# preamp.net
KiCad netlist of a schematic drawn in Altium Designer
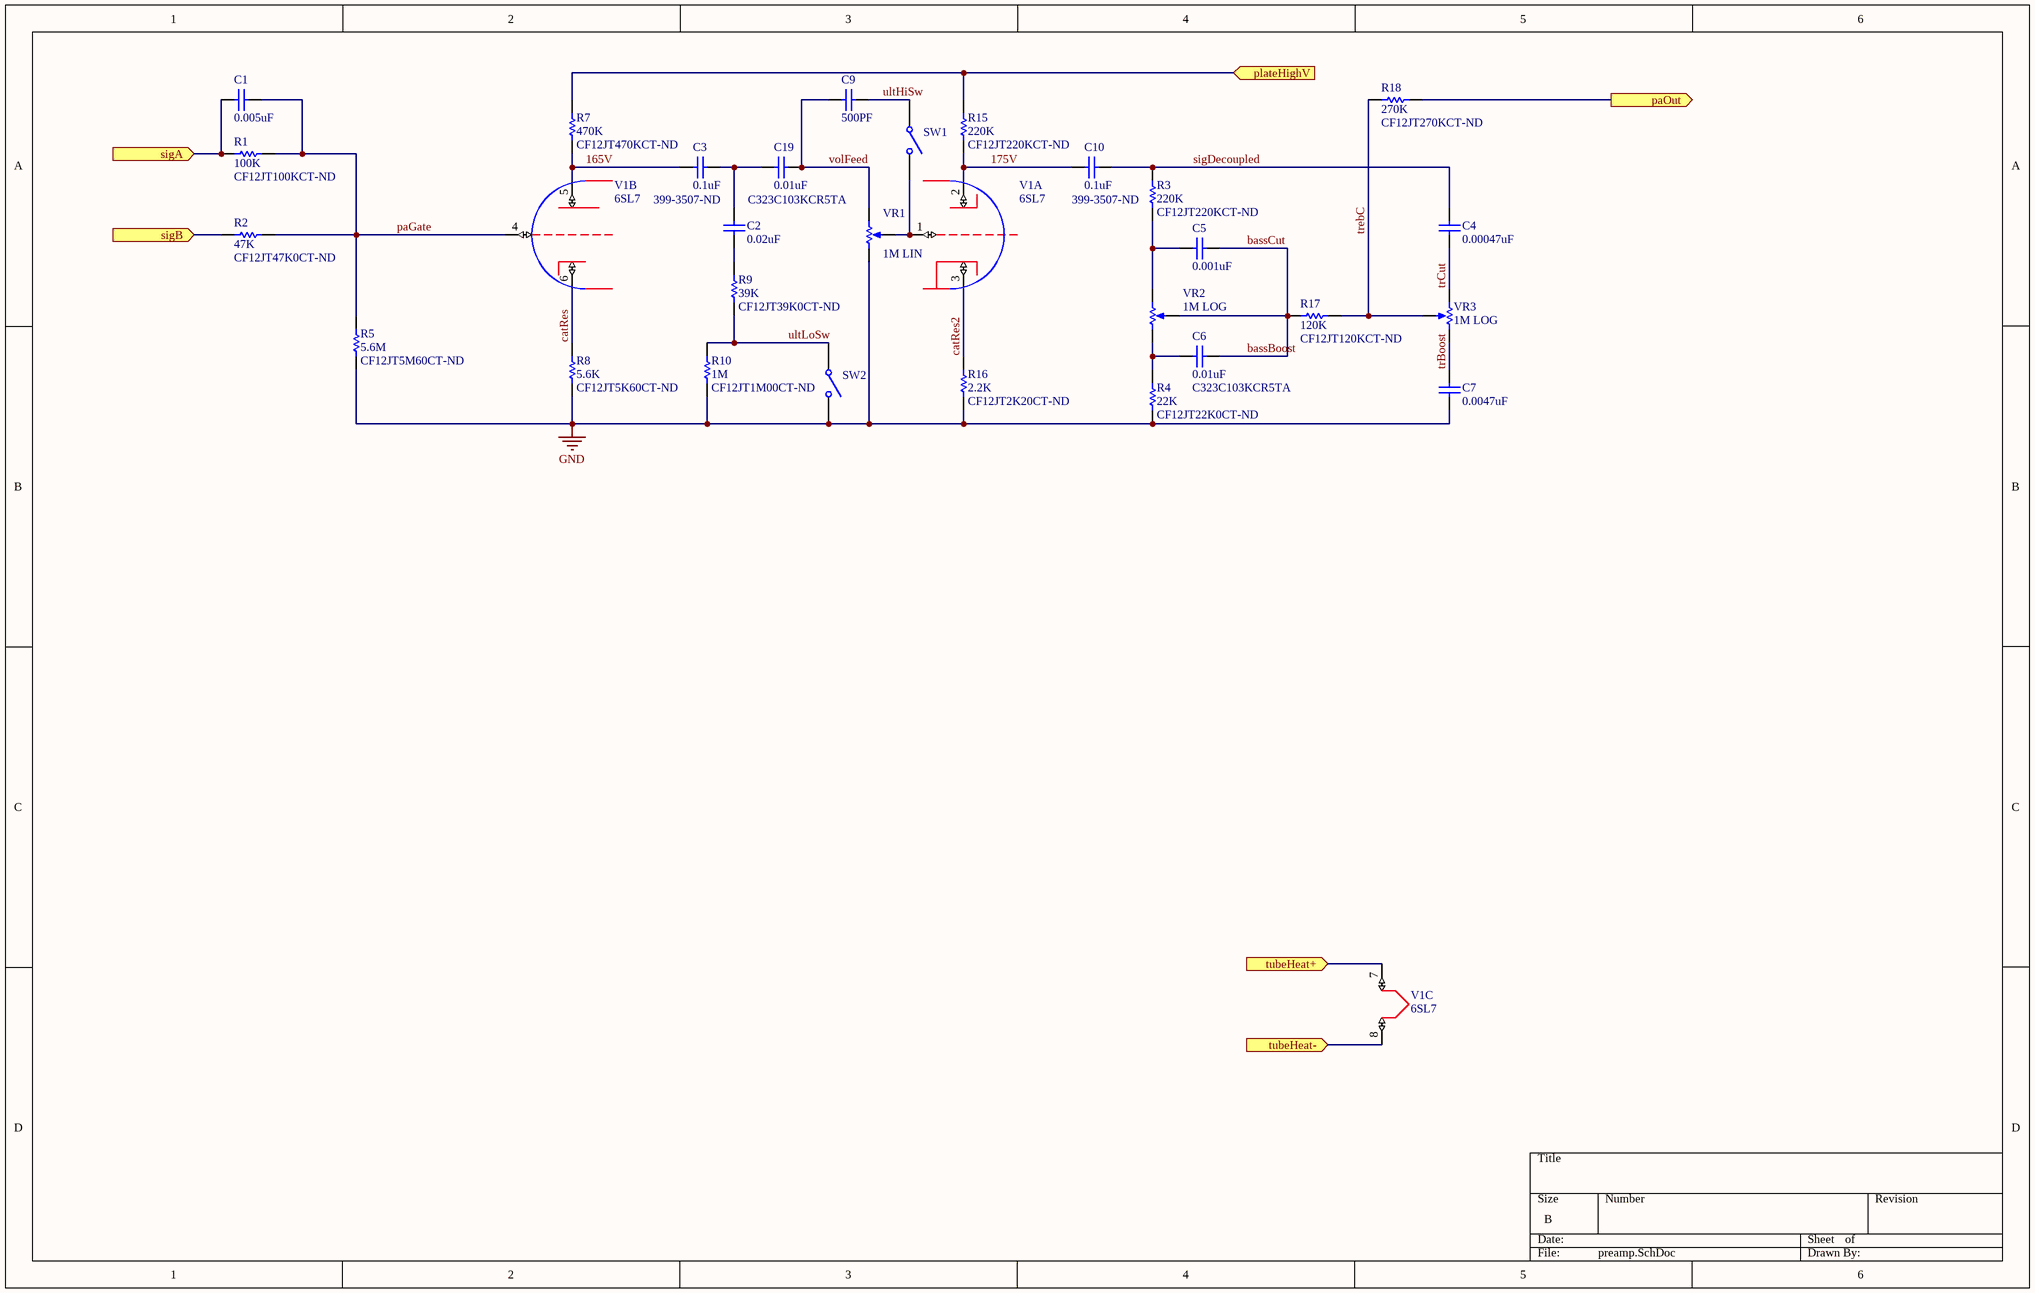
[diagram p0: preamp.SchDoc]

(export (version "E")
  (design (tool "Eeschema 10.0.6"))
  (components
    (comp (ref "C1")
      (value "0.005uF")
      (footprint "RAD-0.3")
      (description "Capacitor")
      (fields (field (name "Comment") "Cap") (field (name "PUBLISHER") "Altium Limited"))
      (libsource (lib "Miscellaneous Devices") (part "Cap"))
    )
    (comp (ref "C2")
      (value "0.02uF")
      (footprint "RAD-0.3")
      (description "Capacitor")
      (fields (field (name "Comment") "Cap") (field (name "PUBLISHER") "Altium Limited"))
      (libsource (lib "Miscellaneous Devices") (part "Cap"))
    )
    (comp (ref "C3")
      (value "0.1uF")
      (footprint "RAD-0.3")
      (description "Capacitor")
      (fields
        (field (name "SUPPLIER PART NUMBER 1") "399-3507-ND")
        (field (name "Comment") "Cap")
        (field (name "PUBLISHER") "Altium Limited")
      )
      (libsource (lib "Miscellaneous Devices") (part "Cap"))
    )
    (comp (ref "C4")
      (value "0.00047uF")
      (footprint "RAD-0.3")
      (description "Capacitor")
      (fields (field (name "Comment") "Cap") (field (name "PUBLISHER") "Altium Limited"))
      (libsource (lib "Miscellaneous Devices") (part "Cap"))
    )
    (comp (ref "C5")
      (value "0.001uF")
      (footprint "RAD-0.3")
      (description "Capacitor")
      (fields (field (name "Comment") "Cap") (field (name "PUBLISHER") "Altium Limited"))
      (libsource (lib "Miscellaneous Devices") (part "Cap"))
    )
    (comp (ref "C6")
      (value "0.01uF")
      (footprint "RAD-0.3")
      (description "Capacitor")
      (fields
        (field (name "SUPPLIER PART NUMBER 1") "C323C103KCR5TA")
        (field (name "Comment") "Cap")
        (field (name "PUBLISHER") "Altium Limited")
      )
      (libsource (lib "Miscellaneous Devices") (part "Cap"))
    )
    (comp (ref "C7")
      (value "0.0047uF")
      (footprint "RAD-0.3")
      (description "Capacitor")
      (fields (field (name "Comment") "Cap") (field (name "PUBLISHER") "Altium Limited"))
      (libsource (lib "Miscellaneous Devices") (part "Cap"))
    )
    (comp (ref "C9")
      (value "500PF")
      (footprint "RAD-0.3")
      (description "Capacitor")
      (fields (field (name "Comment") "Cap") (field (name "PUBLISHER") "Altium Limited"))
      (libsource (lib "Miscellaneous Devices") (part "Cap"))
    )
    (comp (ref "C10")
      (value "0.1uF")
      (footprint "RAD-0.3")
      (description "Capacitor")
      (fields
        (field (name "SUPPLIER PART NUMBER 1") "399-3507-ND")
        (field (name "Comment") "Cap")
        (field (name "PUBLISHER") "Altium Limited")
      )
      (libsource (lib "Miscellaneous Devices") (part "Cap"))
    )
    (comp (ref "C19")
      (value "0.01uF")
      (footprint "RAD-0.3")
      (description "Capacitor")
      (fields
        (field (name "SUPPLIER PART NUMBER 1") "C323C103KCR5TA")
        (field (name "Comment") "Cap")
        (field (name "PUBLISHER") "Altium Limited")
      )
      (libsource (lib "Miscellaneous Devices") (part "Cap"))
    )
    (comp (ref "R1")
      (value "100K")
      (footprint "AXIAL-0.3")
      (description "Resistor")
      (fields
        (field (name "SUPPLIER PART NUMBER 1") "CF12JT100KCT-ND")
        (field (name "Comment") "Res1")
        (field (name "PUBLISHER") "Altium Limited")
      )
      (libsource (lib "Miscellaneous Devices") (part "Res1"))
    )
    (comp (ref "R2")
      (value "47K")
      (footprint "AXIAL-0.3")
      (description "Resistor")
      (fields
        (field (name "SUPPLIER PART NUMBER 1") "CF12JT47K0CT-ND")
        (field (name "Comment") "Res1")
        (field (name "PUBLISHER") "Altium Limited")
      )
      (libsource (lib "Miscellaneous Devices") (part "Res1"))
    )
    (comp (ref "R3")
      (value "220K")
      (footprint "AXIAL-0.3")
      (description "Resistor")
      (fields
        (field (name "SUPPLIER PART NUMBER 1") "CF12JT220KCT-ND")
        (field (name "Comment") "Res1")
        (field (name "PUBLISHER") "Altium Limited")
      )
      (libsource (lib "Miscellaneous Devices") (part "Res1"))
    )
    (comp (ref "R4")
      (value "22K")
      (footprint "AXIAL-0.3")
      (description "Resistor")
      (fields
        (field (name "SUPPLIER PART NUMBER 1") "CF12JT22K0CT-ND")
        (field (name "Comment") "Res1")
        (field (name "PUBLISHER") "Altium Limited")
      )
      (libsource (lib "Miscellaneous Devices") (part "Res1"))
    )
    (comp (ref "R5")
      (value "5.6M")
      (footprint "AXIAL-0.3")
      (description "Resistor")
      (fields
        (field (name "SUPPLIER PART NUMBER 1") "CF12JT5M60CT-ND")
        (field (name "Comment") "Res1")
        (field (name "PUBLISHER") "Altium Limited")
      )
      (libsource (lib "Miscellaneous Devices") (part "Res1"))
    )
    (comp (ref "R7")
      (value "470K")
      (footprint "AXIAL-0.3")
      (description "Resistor")
      (fields
        (field (name "SUPPLIER PART NUMBER 1") "CF12JT470KCT-ND")
        (field (name "Comment") "Res1")
        (field (name "PUBLISHER") "Altium Limited")
      )
      (libsource (lib "Miscellaneous Devices") (part "Res1"))
    )
    (comp (ref "R8")
      (value "5.6K")
      (footprint "AXIAL-0.3")
      (description "Resistor")
      (fields
        (field (name "SUPPLIER PART NUMBER 1") "CF12JT5K60CT-ND")
        (field (name "Comment") "Res1")
        (field (name "PUBLISHER") "Altium Limited")
      )
      (libsource (lib "Miscellaneous Devices") (part "Res1"))
    )
    (comp (ref "R9")
      (value "39K")
      (footprint "AXIAL-0.3")
      (description "Resistor")
      (fields
        (field (name "SUPPLIER PART NUMBER 1") "CF12JT39K0CT-ND")
        (field (name "Comment") "Res1")
        (field (name "PUBLISHER") "Altium Limited")
      )
      (libsource (lib "Miscellaneous Devices") (part "Res1"))
    )
    (comp (ref "R10")
      (value "1M")
      (footprint "AXIAL-0.3")
      (description "Resistor")
      (fields
        (field (name "SUPPLIER PART NUMBER 1") "CF12JT1M00CT-ND")
        (field (name "Comment") "Res1")
        (field (name "PUBLISHER") "Altium Limited")
      )
      (libsource (lib "Miscellaneous Devices") (part "Res1"))
    )
    (comp (ref "R15")
      (value "220K")
      (footprint "AXIAL-0.3")
      (description "Resistor")
      (fields
        (field (name "SUPPLIER PART NUMBER 1") "CF12JT220KCT-ND")
        (field (name "Comment") "Res1")
        (field (name "PUBLISHER") "Altium Limited")
      )
      (libsource (lib "Miscellaneous Devices") (part "Res1"))
    )
    (comp (ref "R16")
      (value "2.2K")
      (footprint "AXIAL-0.3")
      (description "Resistor")
      (fields
        (field (name "SUPPLIER PART NUMBER 1") "CF12JT2K20CT-ND")
        (field (name "Comment") "Res1")
        (field (name "PUBLISHER") "Altium Limited")
      )
      (libsource (lib "Miscellaneous Devices") (part "Res1"))
    )
    (comp (ref "R17")
      (value "120K")
      (footprint "AXIAL-0.3")
      (description "Resistor")
      (fields
        (field (name "SUPPLIER PART NUMBER 1") "CF12JT120KCT-ND")
        (field (name "Comment") "Res1")
        (field (name "PUBLISHER") "Altium Limited")
      )
      (libsource (lib "Miscellaneous Devices") (part "Res1"))
    )
    (comp (ref "R18")
      (value "270K")
      (footprint "AXIAL-0.3")
      (description "Resistor")
      (fields
        (field (name "SUPPLIER PART NUMBER 1") "CF12JT270KCT-ND")
        (field (name "Comment") "Res1")
        (field (name "PUBLISHER") "Altium Limited")
      )
      (libsource (lib "Miscellaneous Devices") (part "Res1"))
    )
    (comp (ref "SW1")
      (value "SW-SPST")
      (footprint "SPST-2")
      (description "Single-Pole, Single-Throw Switch")
      (fields (field (name "PUBLISHER") "Altium Limited"))
      (libsource (lib "Miscellaneous Devices") (part "SW-SPST"))
    )
    (comp (ref "SW2")
      (value "SW-SPST")
      (footprint "SPST-2")
      (description "Single-Pole, Single-Throw Switch")
      (fields (field (name "PUBLISHER") "Altium Limited"))
      (libsource (lib "Miscellaneous Devices") (part "SW-SPST"))
    )
    (comp (ref "V1") (value "6SL7") (footprint "OCTALSOCKET") (libsource (lib "amp_lib") (part "6SL7")))
    (comp (ref "VR1")
      (value "1M LIN")
      (footprint "VR5")
      (description "Potentiometer")
      (fields (field (name "Comment") "RPot") (field (name "PUBLISHER") "Altium Limited"))
      (libsource (lib "Miscellaneous Devices") (part "RPot"))
    )
    (comp (ref "VR2")
      (value "1M LOG")
      (footprint "VR5")
      (description "Potentiometer")
      (fields (field (name "Comment") "RPot") (field (name "PUBLISHER") "Altium Limited"))
      (libsource (lib "Miscellaneous Devices") (part "RPot"))
    )
    (comp (ref "VR3")
      (value "1M LOG")
      (footprint "VR5")
      (description "Potentiometer")
      (fields (field (name "Comment") "RPot") (field (name "PUBLISHER") "Altium Limited"))
      (libsource (lib "Miscellaneous Devices") (part "RPot"))
    )
  )
  (nets
    (net (code "1") (name "/165V") (class "Default")
      (node (ref "C3") (pin "1") (pinfunction "1_1") (pintype "passive"))
      (node (ref "R7") (pin "1") (pinfunction "1_1") (pintype "passive"))
      (node (ref "V1") (pin "5") (pinfunction "topPlate_5") (pintype "bidirectional"))
    )
    (net (code "2") (name "/175V") (class "Default")
      (node (ref "C10") (pin "1") (pinfunction "1_1") (pintype "passive"))
      (node (ref "R15") (pin "1") (pinfunction "1_1") (pintype "passive"))
      (node (ref "V1") (pin "2") (pinfunction "topPlate_2") (pintype "bidirectional"))
    )
    (net (code "3") (name "/bassBoost") (class "Default")
      (node (ref "C5") (pin "2") (pinfunction "2_2") (pintype "passive"))
      (node (ref "C6") (pin "2") (pinfunction "2_2") (pintype "passive"))
      (node (ref "R17") (pin "1") (pinfunction "1_1") (pintype "passive"))
      (node (ref "VR2") (pin "3") (pinfunction "TAP_3") (pintype "passive"))
    )
    (net (code "4") (name "/catRes") (class "Default")
      (node (ref "R8") (pin "2") (pinfunction "2_2") (pintype "passive"))
      (node (ref "V1") (pin "6") (pinfunction "topPlate_6") (pintype "bidirectional"))
    )
    (net (code "5") (name "/catRes2") (class "Default")
      (node (ref "R16") (pin "2") (pinfunction "2_2") (pintype "passive"))
      (node (ref "V1") (pin "3") (pinfunction "topPlate_3") (pintype "bidirectional"))
    )
    (net (code "6") (name "/paGate") (class "Default")
      (node (ref "C1") (pin "1") (pinfunction "1_1") (pintype "passive"))
      (node (ref "R1") (pin "2") (pinfunction "2_2") (pintype "passive"))
      (node (ref "R2") (pin "2") (pinfunction "2_2") (pintype "passive"))
      (node (ref "R5") (pin "2") (pinfunction "2_2") (pintype "passive"))
      (node (ref "V1") (pin "4") (pinfunction "gate_4") (pintype "bidirectional"))
    )
    (net (code "7") (name "/paOut") (class "Default")
      (node (ref "R18") (pin "2") (pinfunction "2_2") (pintype "passive"))
    )
    (net (code "8") (name "/plateHighV") (class "Default")
      (node (ref "R15") (pin "2") (pinfunction "2_2") (pintype "passive"))
      (node (ref "R7") (pin "2") (pinfunction "2_2") (pintype "passive"))
    )
    (net (code "9") (name "/sigA") (class "Default")
      (node (ref "C1") (pin "2") (pinfunction "2_2") (pintype "passive"))
      (node (ref "R1") (pin "1") (pinfunction "1_1") (pintype "passive"))
    )
    (net (code "10") (name "/sigB") (class "Default")
      (node (ref "R2") (pin "1") (pinfunction "1_1") (pintype "passive"))
    )
    (net (code "11") (name "/sigDecoupled") (class "Default")
      (node (ref "C10") (pin "2") (pinfunction "2_2") (pintype "passive"))
      (node (ref "C4") (pin "2") (pinfunction "2_2") (pintype "passive"))
      (node (ref "R3") (pin "2") (pinfunction "2_2") (pintype "passive"))
    )
    (net (code "12") (name "/trBoost") (class "Default")
      (node (ref "C7") (pin "2") (pinfunction "2_2") (pintype "passive"))
      (node (ref "VR3") (pin "2") (pinfunction "BOT_2") (pintype "passive"))
    )
    (net (code "13") (name "/trCut") (class "Default")
      (node (ref "C4") (pin "1") (pinfunction "1_1") (pintype "passive"))
      (node (ref "VR3") (pin "1") (pinfunction "TOP_1") (pintype "passive"))
    )
    (net (code "14") (name "/trebC") (class "Default")
      (node (ref "R17") (pin "2") (pinfunction "2_2") (pintype "passive"))
      (node (ref "R18") (pin "1") (pinfunction "1_1") (pintype "passive"))
      (node (ref "VR3") (pin "3") (pinfunction "TAP_3") (pintype "passive"))
    )
    (net (code "15") (name "/tubeHeat+") (class "Default")
      (node (ref "V1") (pin "7") (pinfunction "7_7") (pintype "bidirectional"))
    )
    (net (code "16") (name "/tubeHeat-") (class "Default")
      (node (ref "V1") (pin "8") (pinfunction "8_8") (pintype "bidirectional"))
    )
    (net (code "17") (name "/ultHiSw") (class "Default")
      (node (ref "C9") (pin "1") (pinfunction "1_1") (pintype "passive"))
      (node (ref "SW1") (pin "1") (pinfunction "COMMON_1") (pintype "passive"))
    )
    (net (code "18") (name "/ultLoSw") (class "Default")
      (node (ref "R10") (pin "2") (pinfunction "2_2") (pintype "passive"))
      (node (ref "R9") (pin "1") (pinfunction "1_1") (pintype "passive"))
      (node (ref "SW2") (pin "1") (pinfunction "COMMON_1") (pintype "passive"))
    )
    (net (code "19") (name "/volFeed") (class "Default")
      (node (ref "C19") (pin "2") (pinfunction "2_2") (pintype "passive"))
      (node (ref "C9") (pin "2") (pinfunction "2_2") (pintype "passive"))
      (node (ref "VR1") (pin "2") (pinfunction "BOT_2") (pintype "passive"))
    )
    (net (code "20") (name "GND") (class "Default")
      (node (ref "C7") (pin "1") (pinfunction "1_1") (pintype "passive"))
      (node (ref "R10") (pin "1") (pinfunction "1_1") (pintype "passive"))
      (node (ref "R16") (pin "1") (pinfunction "1_1") (pintype "passive"))
      (node (ref "R4") (pin "1") (pinfunction "1_1") (pintype "passive"))
      (node (ref "R5") (pin "1") (pinfunction "1_1") (pintype "passive"))
      (node (ref "R8") (pin "1") (pinfunction "1_1") (pintype "passive"))
      (node (ref "SW2") (pin "2") (pinfunction "NO_2") (pintype "passive"))
      (node (ref "VR1") (pin "1") (pinfunction "TOP_1") (pintype "passive"))
    )
    (net (code "21") (name "Net-(C2-Pad1)") (class "Default")
      (node (ref "C2") (pin "1") (pinfunction "1_1") (pintype "passive"))
      (node (ref "R9") (pin "2") (pinfunction "2_2") (pintype "passive"))
    )
    (net (code "22") (name "Net-(C19-Pad1)") (class "Default")
      (node (ref "C19") (pin "1") (pinfunction "1_1") (pintype "passive"))
      (node (ref "C2") (pin "2") (pinfunction "2_2") (pintype "passive"))
      (node (ref "C3") (pin "2") (pinfunction "2_2") (pintype "passive"))
    )
    (net (code "23") (name "Net-(SW1-NO)") (class "Default")
      (node (ref "SW1") (pin "2") (pinfunction "NO_2") (pintype "passive"))
      (node (ref "V1") (pin "1") (pinfunction "gate_1") (pintype "bidirectional"))
      (node (ref "VR1") (pin "3") (pinfunction "TAP_3") (pintype "passive"))
    )
    (net (code "24") (name "Net-(VR2-BOT)") (class "Default")
      (node (ref "C5") (pin "1") (pinfunction "1_1") (pintype "passive"))
      (node (ref "R3") (pin "1") (pinfunction "1_1") (pintype "passive"))
      (node (ref "VR2") (pin "2") (pinfunction "BOT_2") (pintype "passive"))
    )
    (net (code "25") (name "Net-(VR2-TOP)") (class "Default")
      (node (ref "C6") (pin "1") (pinfunction "1_1") (pintype "passive"))
      (node (ref "R4") (pin "2") (pinfunction "2_2") (pintype "passive"))
      (node (ref "VR2") (pin "1") (pinfunction "TOP_1") (pintype "passive"))
    )
  )
)
